# Arduino_FPGA_Top-Level_Interface.net
KiCad netlist of a schematic drawn in Altium Designer
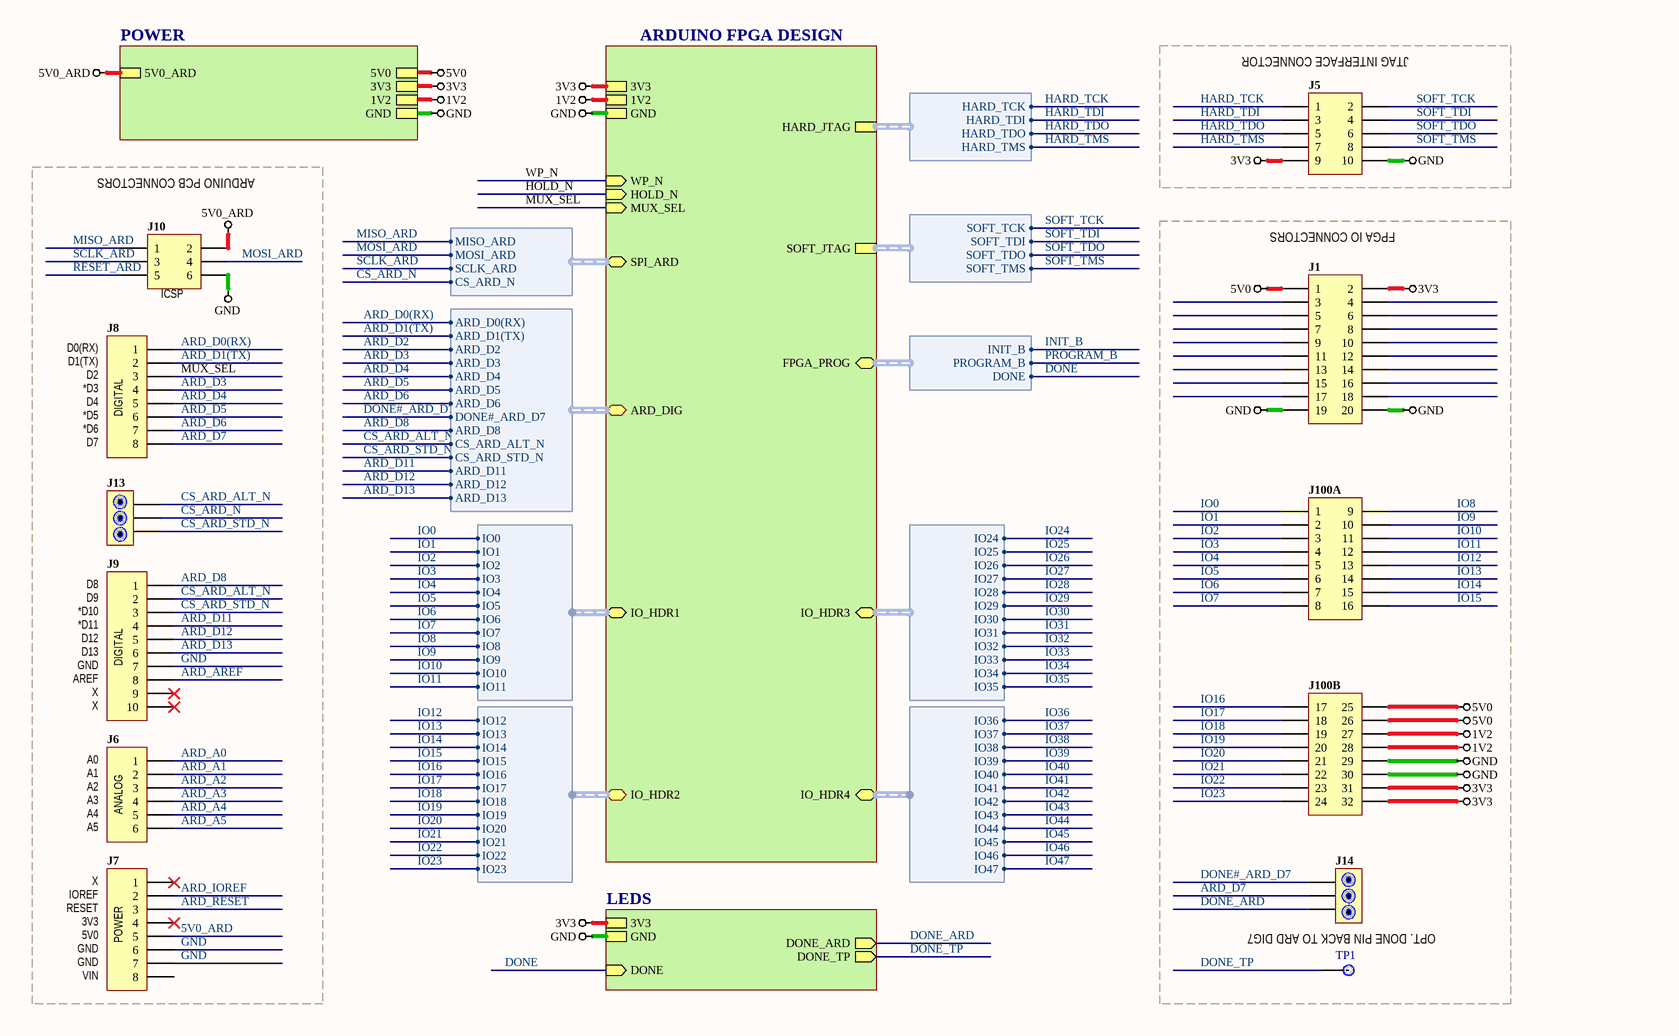
[diagram p0: Arduino FPGA Top-Level Interface.SchDoc]

(export (version "E")
  (design (tool "Eeschema 10.0.6"))
  (components
    (comp (ref "J1")
      (value "Header 10X2")
      (footprint "HEADER_10X2")
      (description "Header, 10-Pin, Dual row")
      (fields (field (name "PUBLISHER") "Altium Limited"))
      (libsource (lib "Miscellaneous Connectors") (part "Header 10X2"))
    )
    (comp (ref "J5")
      (value "Header 5X2")
      (footprint "HDR2X5")
      (description "Header, 5-Pin, Dual row")
      (fields (field (name "PUBLISHER") "Altium Limited"))
      (libsource (lib "Miscellaneous Connectors") (part "Header 5X2"))
    )
    (comp (ref "J6")
      (value "Header 6")
      (footprint "1X06")
      (description "Header, 6-Pin")
      (fields (field (name "PUBLISHER") "Altium Limited"))
      (libsource (lib "Miscellaneous Connectors") (part "Header 6"))
    )
    (comp (ref "J7")
      (value "Header 8")
      (footprint "1X08")
      (description "Header, 8-Pin")
      (fields (field (name "PUBLISHER") "Altium Limited"))
      (libsource (lib "Miscellaneous Connectors") (part "Header 8"))
    )
    (comp (ref "J8")
      (value "Header 8")
      (footprint "1X08")
      (description "Header, 8-Pin")
      (fields (field (name "PUBLISHER") "Altium Limited"))
      (libsource (lib "Miscellaneous Connectors") (part "Header 8"))
    )
    (comp (ref "J9")
      (value "Header 10")
      (footprint "1X10@1")
      (description "Header, 10-Pin")
      (fields (field (name "PUBLISHER") "Altium Limited"))
      (libsource (lib "Miscellaneous Connectors") (part "Header 10"))
    )
    (comp (ref "J10")
      (value "Header 3X2")
      (footprint "2X03")
      (description "Header, 3-Pin, Dual row")
      (fields (field (name "PUBLISHER") "Altium Limited"))
      (libsource (lib "Miscellaneous Connectors") (part "Header 3X2"))
    )
    (comp (ref "J13")
      (value "3-WAY JUMPER")
      (footprint "HDR1X3")
      (description "3-Way Jumper - Center Output")
      (libsource (lib "3-WAY JUMPER") (part "3-WAY JUMPER"))
    )
    (comp (ref "J14")
      (value "3-WAY JUMPER")
      (footprint "HDR1X3")
      (description "3-Way Jumper - Center Output")
      (libsource (lib "") (part "3-WAY JUMPER_1"))
    )
    (comp (ref "J100")
      (value "ARR_32P")
      (footprint "ARR_100X100X32P")
      (description "Pad Array - 32 Pins 100X100mil spacing")
      (libsource (lib "ARR_32P") (part "ARR_32P"))
    )
    (comp (ref "TP1")
      (value "TESTPOINT_TH")
      (footprint "TESTPOINT_TH")
      (libsource (lib "TESTPOINT_TH") (part "TESTPOINT_TH"))
    )
  )
  (nets
    (net (code "10") (name "/ARD_A0") (class "Default")
      (node (ref "J6") (pin "1") (pinfunction "1_1") (pintype "passive"))
    )
    (net (code "11") (name "/ARD_A1") (class "Default")
      (node (ref "J6") (pin "2") (pinfunction "2_2") (pintype "passive"))
    )
    (net (code "12") (name "/ARD_A2") (class "Default")
      (node (ref "J6") (pin "3") (pinfunction "3_3") (pintype "passive"))
    )
    (net (code "13") (name "/ARD_A3") (class "Default")
      (node (ref "J6") (pin "4") (pinfunction "4_4") (pintype "passive"))
    )
    (net (code "14") (name "/ARD_A4") (class "Default")
      (node (ref "J6") (pin "5") (pinfunction "5_5") (pintype "passive"))
    )
    (net (code "15") (name "/ARD_A5") (class "Default")
      (node (ref "J6") (pin "6") (pinfunction "6_6") (pintype "passive"))
    )
    (net (code "16") (name "/ARD_AREF") (class "Default")
      (node (ref "J9") (pin "8") (pinfunction "8_8") (pintype "passive"))
    )
    (net (code "17") (name "/ARD_D0(RX)") (class "Default")
      (node (ref "J8") (pin "1") (pinfunction "1_1") (pintype "passive"))
    )
    (net (code "18") (name "/ARD_D1(TX)") (class "Default")
      (node (ref "J8") (pin "2") (pinfunction "2_2") (pintype "passive"))
    )
    (net (code "20") (name "/ARD_D3") (class "Default")
      (node (ref "J8") (pin "4") (pinfunction "4_4") (pintype "passive"))
    )
    (net (code "21") (name "/ARD_D4") (class "Default")
      (node (ref "J8") (pin "5") (pinfunction "5_5") (pintype "passive"))
    )
    (net (code "22") (name "/ARD_D5") (class "Default")
      (node (ref "J8") (pin "6") (pinfunction "6_6") (pintype "passive"))
    )
    (net (code "23") (name "/ARD_D6") (class "Default")
      (node (ref "J8") (pin "7") (pinfunction "7_7") (pintype "passive"))
    )
    (net (code "24") (name "/ARD_D7") (class "Default")
      (node (ref "J14") (pin "2") (pinfunction "2_2") (pintype "passive"))
      (node (ref "J8") (pin "8") (pinfunction "8_8") (pintype "passive"))
    )
    (net (code "25") (name "/ARD_D8") (class "Default")
      (node (ref "J9") (pin "1") (pinfunction "1_1") (pintype "passive"))
    )
    (net (code "26") (name "/ARD_D11") (class "Default")
      (node (ref "J9") (pin "4") (pinfunction "4_4") (pintype "passive"))
    )
    (net (code "27") (name "/ARD_D12") (class "Default")
      (node (ref "J9") (pin "5") (pinfunction "5_5") (pintype "passive"))
    )
    (net (code "28") (name "/ARD_D13") (class "Default")
      (node (ref "J9") (pin "6") (pinfunction "6_6") (pintype "passive"))
    )
    (net (code "29") (name "/ARD_IOREF") (class "Default")
      (node (ref "J7") (pin "2") (pinfunction "2_2") (pintype "passive"))
    )
    (net (code "30") (name "/ARD_RESET") (class "Default")
      (node (ref "J7") (pin "3") (pinfunction "3_3") (pintype "passive"))
    )
    (net (code "31") (name "/CS_ARD_ALT_N") (class "Default")
      (node (ref "J13") (pin "3") (pinfunction "3_3") (pintype "passive"))
      (node (ref "J9") (pin "2") (pinfunction "2_2") (pintype "passive"))
    )
    (net (code "32") (name "/CS_ARD_N") (class "Default")
      (node (ref "J13") (pin "2") (pinfunction "2_2") (pintype "passive"))
    )
    (net (code "33") (name "/CS_ARD_STD_N") (class "Default")
      (node (ref "J13") (pin "1") (pinfunction "1_1") (pintype "passive"))
      (node (ref "J9") (pin "3") (pinfunction "3_3") (pintype "passive"))
    )
    (net (code "35") (name "/DONE#_ARD_D7") (class "Default")
      (node (ref "J14") (pin "3") (pinfunction "3_3") (pintype "passive"))
    )
    (net (code "36") (name "/DONE_ARD") (class "Default")
      (node (ref "J14") (pin "1") (pinfunction "1_1") (pintype "passive"))
    )
    (net (code "37") (name "/DONE_TP") (class "Default")
      (node (ref "TP1") (pin "1") (pinfunction "1_1") (pintype "passive"))
    )
    (net (code "38") (name "/HARD_TCK") (class "Default")
      (node (ref "J5") (pin "1") (pinfunction "1_1") (pintype "passive"))
    )
    (net (code "39") (name "/HARD_TDI") (class "Default")
      (node (ref "J5") (pin "3") (pinfunction "3_3") (pintype "passive"))
    )
    (net (code "40") (name "/HARD_TDO") (class "Default")
      (node (ref "J5") (pin "5") (pinfunction "5_5") (pintype "passive"))
    )
    (net (code "41") (name "/HARD_TMS") (class "Default")
      (node (ref "J5") (pin "7") (pinfunction "7_7") (pintype "passive"))
    )
    (net (code "44") (name "/IO0") (class "Default")
      (node (ref "J100") (pin "1") (pinfunction "1_1") (pintype "passive"))
    )
    (net (code "45") (name "/IO1") (class "Default")
      (node (ref "J100") (pin "2") (pinfunction "2_2") (pintype "passive"))
    )
    (net (code "46") (name "/IO2") (class "Default")
      (node (ref "J100") (pin "3") (pinfunction "3_3") (pintype "passive"))
    )
    (net (code "47") (name "/IO3") (class "Default")
      (node (ref "J100") (pin "4") (pinfunction "4_4") (pintype "passive"))
    )
    (net (code "48") (name "/IO4") (class "Default")
      (node (ref "J100") (pin "5") (pinfunction "5_5") (pintype "passive"))
    )
    (net (code "49") (name "/IO5") (class "Default")
      (node (ref "J100") (pin "6") (pinfunction "6_6") (pintype "passive"))
    )
    (net (code "50") (name "/IO6") (class "Default")
      (node (ref "J100") (pin "7") (pinfunction "7_7") (pintype "passive"))
    )
    (net (code "51") (name "/IO7") (class "Default")
      (node (ref "J100") (pin "8") (pinfunction "8_8") (pintype "passive"))
    )
    (net (code "52") (name "/IO8") (class "Default")
      (node (ref "J100") (pin "9") (pinfunction "9_9") (pintype "passive"))
    )
    (net (code "53") (name "/IO9") (class "Default")
      (node (ref "J100") (pin "10") (pinfunction "10_10") (pintype "passive"))
    )
    (net (code "54") (name "/IO10") (class "Default")
      (node (ref "J100") (pin "11") (pinfunction "11_11") (pintype "passive"))
    )
    (net (code "55") (name "/IO11") (class "Default")
      (node (ref "J100") (pin "12") (pinfunction "12_12") (pintype "passive"))
    )
    (net (code "56") (name "/IO12") (class "Default")
      (node (ref "J100") (pin "13") (pinfunction "13_13") (pintype "passive"))
    )
    (net (code "57") (name "/IO13") (class "Default")
      (node (ref "J100") (pin "14") (pinfunction "14_14") (pintype "passive"))
    )
    (net (code "58") (name "/IO14") (class "Default")
      (node (ref "J100") (pin "15") (pinfunction "15_15") (pintype "passive"))
    )
    (net (code "59") (name "/IO15") (class "Default")
      (node (ref "J100") (pin "16") (pinfunction "16_16") (pintype "passive"))
    )
    (net (code "60") (name "/IO16") (class "Default")
      (node (ref "J100") (pin "17") (pinfunction "17_17") (pintype "passive"))
    )
    (net (code "61") (name "/IO17") (class "Default")
      (node (ref "J100") (pin "18") (pinfunction "18_18") (pintype "passive"))
    )
    (net (code "62") (name "/IO18") (class "Default")
      (node (ref "J100") (pin "19") (pinfunction "19_19") (pintype "passive"))
    )
    (net (code "63") (name "/IO19") (class "Default")
      (node (ref "J100") (pin "20") (pinfunction "20_20") (pintype "passive"))
    )
    (net (code "64") (name "/IO20") (class "Default")
      (node (ref "J100") (pin "21") (pinfunction "21_21") (pintype "passive"))
    )
    (net (code "65") (name "/IO21") (class "Default")
      (node (ref "J100") (pin "22") (pinfunction "22_22") (pintype "passive"))
    )
    (net (code "66") (name "/IO22") (class "Default")
      (node (ref "J100") (pin "23") (pinfunction "23_23") (pintype "passive"))
    )
    (net (code "67") (name "/IO23") (class "Default")
      (node (ref "J100") (pin "24") (pinfunction "24_24") (pintype "passive"))
    )
    (net (code "92") (name "/MISO_ARD") (class "Default")
      (node (ref "J10") (pin "1") (pinfunction "1_1") (pintype "passive"))
    )
    (net (code "93") (name "/MOSI_ARD") (class "Default")
      (node (ref "J10") (pin "4") (pinfunction "4_4") (pintype "passive"))
    )
    (net (code "94") (name "/MUX_SEL") (class "Default")
      (node (ref "J8") (pin "3") (pinfunction "3_3") (pintype "passive"))
    )
    (net (code "96") (name "/RESET_ARD") (class "Default")
      (node (ref "J10") (pin "5") (pinfunction "5_5") (pintype "passive"))
    )
    (net (code "97") (name "/SCLK_ARD") (class "Default")
      (node (ref "J10") (pin "3") (pinfunction "3_3") (pintype "passive"))
    )
    (net (code "98") (name "/SOFT_TCK") (class "Default")
      (node (ref "J5") (pin "2") (pinfunction "2_2") (pintype "passive"))
    )
    (net (code "99") (name "/SOFT_TDI") (class "Default")
      (node (ref "J5") (pin "4") (pinfunction "4_4") (pintype "passive"))
    )
    (net (code "100") (name "/SOFT_TDO") (class "Default")
      (node (ref "J5") (pin "6") (pinfunction "6_6") (pintype "passive"))
    )
    (net (code "101") (name "/SOFT_TMS") (class "Default")
      (node (ref "J5") (pin "8") (pinfunction "8_8") (pintype "passive"))
    )
    (net (code "112") (name "1V2") (class "Default")
      (node (ref "J100") (pin "27") (pinfunction "27_27") (pintype "passive"))
      (node (ref "J100") (pin "28") (pinfunction "28_28") (pintype "passive"))
    )
    (net (code "113") (name "3V3") (class "Default")
      (node (ref "J1") (pin "2") (pinfunction "2_2") (pintype "passive"))
      (node (ref "J100") (pin "31") (pinfunction "31_31") (pintype "passive"))
      (node (ref "J100") (pin "32") (pinfunction "32_32") (pintype "passive"))
      (node (ref "J5") (pin "9") (pinfunction "9_9") (pintype "passive"))
    )
    (net (code "114") (name "5V0") (class "Default")
      (node (ref "J1") (pin "1") (pinfunction "1_1") (pintype "passive"))
      (node (ref "J100") (pin "25") (pinfunction "25_25") (pintype "passive"))
      (node (ref "J100") (pin "26") (pinfunction "26_26") (pintype "passive"))
    )
    (net (code "115") (name "5V0_ARD") (class "Default")
      (node (ref "J7") (pin "5") (pinfunction "5_5") (pintype "passive"))
    )
    (net (code "116") (name "GND") (class "Default")
      (node (ref "J1") (pin "19") (pinfunction "19_19") (pintype "passive"))
      (node (ref "J1") (pin "20") (pinfunction "20_20") (pintype "passive"))
      (node (ref "J10") (pin "6") (pinfunction "6_6") (pintype "passive"))
      (node (ref "J100") (pin "29") (pinfunction "29_29") (pintype "passive"))
      (node (ref "J100") (pin "30") (pinfunction "30_30") (pintype "passive"))
      (node (ref "J5") (pin "10") (pinfunction "10_10") (pintype "passive"))
      (node (ref "J7") (pin "6") (pinfunction "6_6") (pintype "passive"))
      (node (ref "J7") (pin "7") (pinfunction "7_7") (pintype "passive"))
      (node (ref "J9") (pin "7") (pinfunction "7_7") (pintype "passive"))
    )
    (net (code "117") (name "unconnected-(J1-Pad3)") (class "Default")
      (node (ref "J1") (pin "3") (pinfunction "3_3") (pintype "passive"))
    )
    (net (code "118") (name "unconnected-(J1-Pad4)") (class "Default")
      (node (ref "J1") (pin "4") (pinfunction "4_4") (pintype "passive"))
    )
    (net (code "119") (name "unconnected-(J1-Pad5)") (class "Default")
      (node (ref "J1") (pin "5") (pinfunction "5_5") (pintype "passive"))
    )
    (net (code "120") (name "unconnected-(J1-Pad6)") (class "Default")
      (node (ref "J1") (pin "6") (pinfunction "6_6") (pintype "passive"))
    )
    (net (code "121") (name "unconnected-(J1-Pad7)") (class "Default")
      (node (ref "J1") (pin "7") (pinfunction "7_7") (pintype "passive"))
    )
    (net (code "122") (name "unconnected-(J1-Pad8)") (class "Default")
      (node (ref "J1") (pin "8") (pinfunction "8_8") (pintype "passive"))
    )
    (net (code "123") (name "unconnected-(J1-Pad9)") (class "Default")
      (node (ref "J1") (pin "9") (pinfunction "9_9") (pintype "passive"))
    )
    (net (code "124") (name "unconnected-(J1-Pad10)") (class "Default")
      (node (ref "J1") (pin "10") (pinfunction "10_10") (pintype "passive"))
    )
    (net (code "125") (name "unconnected-(J1-Pad11)") (class "Default")
      (node (ref "J1") (pin "11") (pinfunction "11_11") (pintype "passive"))
    )
    (net (code "126") (name "unconnected-(J1-Pad12)") (class "Default")
      (node (ref "J1") (pin "12") (pinfunction "12_12") (pintype "passive"))
    )
    (net (code "127") (name "unconnected-(J1-Pad13)") (class "Default")
      (node (ref "J1") (pin "13") (pinfunction "13_13") (pintype "passive"))
    )
    (net (code "128") (name "unconnected-(J1-Pad14)") (class "Default")
      (node (ref "J1") (pin "14") (pinfunction "14_14") (pintype "passive"))
    )
    (net (code "129") (name "unconnected-(J1-Pad15)") (class "Default")
      (node (ref "J1") (pin "15") (pinfunction "15_15") (pintype "passive"))
    )
    (net (code "130") (name "unconnected-(J1-Pad16)") (class "Default")
      (node (ref "J1") (pin "16") (pinfunction "16_16") (pintype "passive"))
    )
    (net (code "131") (name "unconnected-(J1-Pad17)") (class "Default")
      (node (ref "J1") (pin "17") (pinfunction "17_17") (pintype "passive"))
    )
    (net (code "132") (name "unconnected-(J1-Pad18)") (class "Default")
      (node (ref "J1") (pin "18") (pinfunction "18_18") (pintype "passive"))
    )
    (net (code "133") (name "unconnected-(J7-Pad1)") (class "Default")
      (node (ref "J7") (pin "1") (pinfunction "1_1") (pintype "passive+no_connect"))
    )
    (net (code "134") (name "unconnected-(J7-Pad4)") (class "Default")
      (node (ref "J7") (pin "4") (pinfunction "4_4") (pintype "passive+no_connect"))
    )
    (net (code "135") (name "unconnected-(J7-Pad8)") (class "Default")
      (node (ref "J7") (pin "8") (pinfunction "8_8") (pintype "passive"))
    )
    (net (code "136") (name "unconnected-(J9-Pad9)") (class "Default")
      (node (ref "J9") (pin "9") (pinfunction "9_9") (pintype "passive+no_connect"))
    )
    (net (code "137") (name "unconnected-(J9-Pad10)") (class "Default")
      (node (ref "J9") (pin "10") (pinfunction "10_10") (pintype "passive+no_connect"))
    )
    (net (code "138") (name "unconnected-(J10-Pad2)") (class "Default")
      (node (ref "J10") (pin "2") (pinfunction "2_2") (pintype "passive"))
    )
  )
)
